# Core429IBaseBoardVerE.net
KiCad netlist of a schematic drawn in Altium Designer
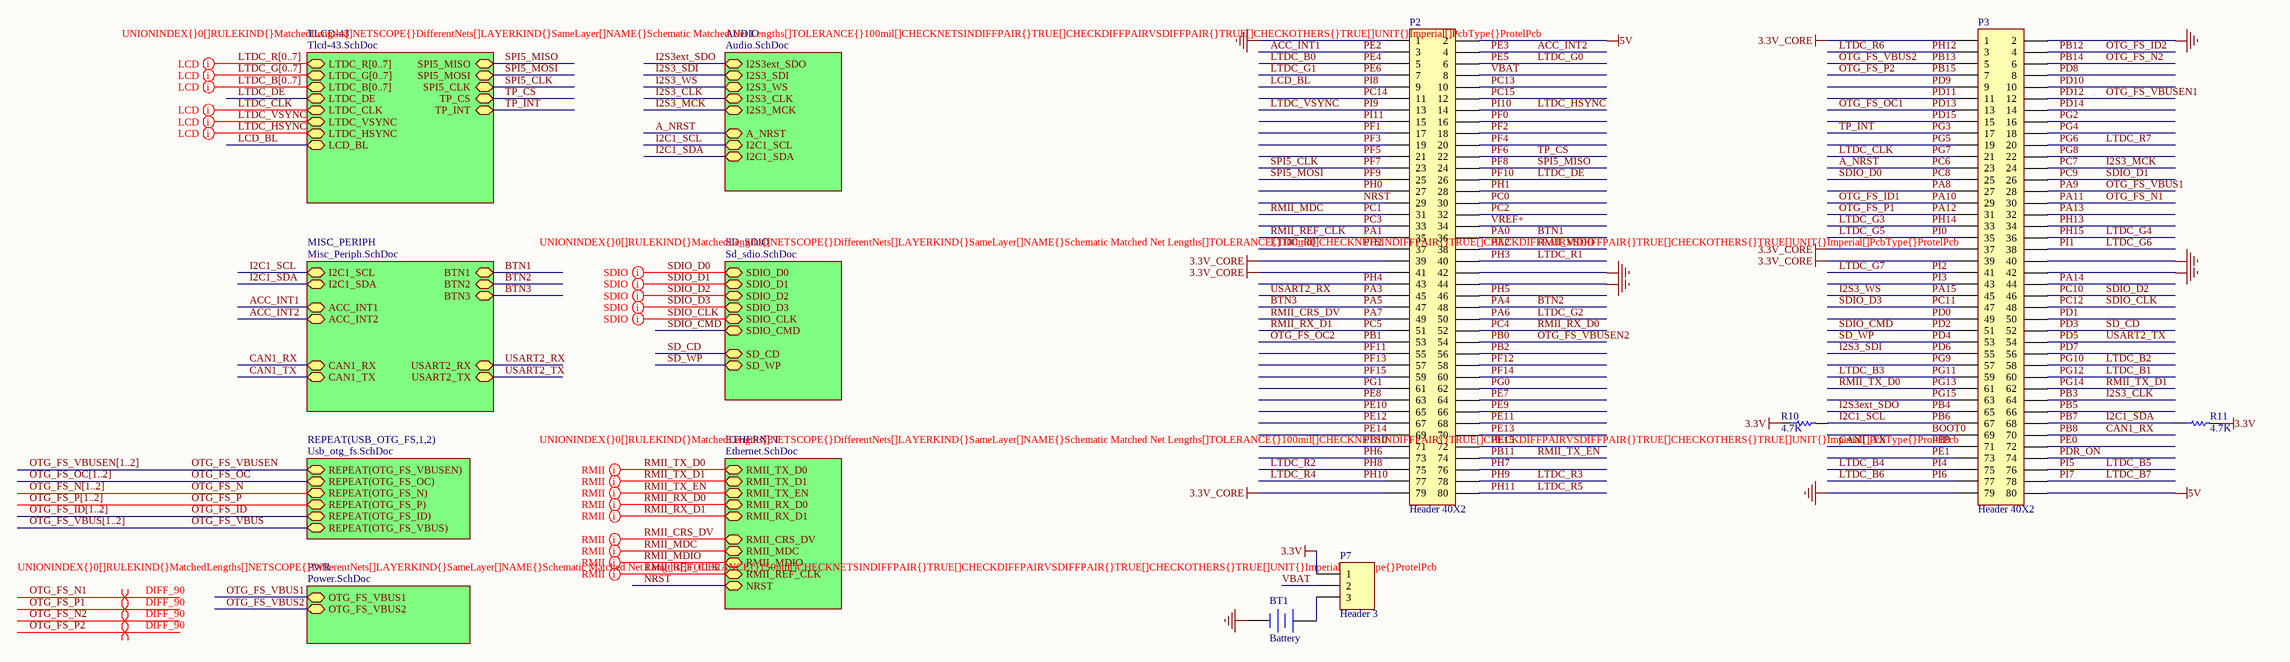
[diagram p0: Core429IBaseBoardVerE.SchDoc]

(export (version "E")
  (design (tool "Eeschema 10.0.6"))
  (components
    (comp (ref "BT1")
      (value "Battery")
      (footprint "PN3000")
      (description "Multicell Battery")
      (libsource (lib "Core429IBaseBoardVerE") (part "Battery"))
    )
    (comp (ref "P2")
      (value "Header 40X2")
      (footprint "SHDR2X40")
      (description "Header, 40-Pin, Dual row")
      (libsource (lib "Core429IBaseBoard") (part "Header 40X2"))
    )
    (comp (ref "P3")
      (value "Header 40X2")
      (footprint "SHDR2X40")
      (description "Header, 40-Pin, Dual row")
      (libsource (lib "Core429IBaseBoard") (part "Header 40X2"))
    )
    (comp (ref "P7")
      (value "Header 3")
      (footprint "HDR1X3")
      (description "Header, 3-Pin")
      (libsource (lib "Core429IBaseBoardVerE") (part "Header 3"))
    )
    (comp (ref "R10")
      (value "4.7K")
      (footprint "RESC2012N")
      (description "Resistor")
      (fields (field (name "Comment") "Res"))
      (libsource (lib "Core429IBaseBoardVerE") (part "Res"))
    )
    (comp (ref "R11")
      (value "4.7K")
      (footprint "RESC2012N")
      (description "Resistor")
      (fields (field (name "Comment") "Res"))
      (libsource (lib "Core429IBaseBoardVerE") (part "Res"))
    )
  )
  (nets
    (net (code "1") (name "/ACC_INT1") (class "Default")
      (node (ref "P2") (pin "3") (pinfunction "3_3") (pintype "passive"))
    )
    (net (code "2") (name "/ACC_INT2") (class "Default")
      (node (ref "P2") (pin "4") (pinfunction "4_4") (pintype "passive"))
    )
    (net (code "3") (name "/A_NRST") (class "Default")
      (node (ref "P3") (pin "23") (pinfunction "23_23") (pintype "passive"))
    )
    (net (code "4") (name "/BOOT0") (class "Default")
      (node (ref "P3") (pin "69") (pinfunction "69_69") (pintype "passive"))
    )
    (net (code "5") (name "/BTN1") (class "Default")
      (node (ref "P2") (pin "36") (pinfunction "36_36") (pintype "passive"))
    )
    (net (code "6") (name "/BTN2") (class "Default")
      (node (ref "P2") (pin "48") (pinfunction "48_48") (pintype "passive"))
    )
    (net (code "7") (name "/BTN3") (class "Default")
      (node (ref "P2") (pin "47") (pinfunction "47_47") (pintype "passive"))
    )
    (net (code "8") (name "/CAN1_RX") (class "Default")
      (node (ref "P3") (pin "70") (pinfunction "70_70") (pintype "passive"))
    )
    (net (code "9") (name "/CAN1_TX") (class "Default")
      (node (ref "P3") (pin "71") (pinfunction "71_71") (pintype "passive"))
    )
    (net (code "10") (name "/I2C1_SCL") (class "Default")
      (node (ref "P3") (pin "67") (pinfunction "67_67") (pintype "passive"))
      (node (ref "R10") (pin "2") (pinfunction "2_2") (pintype "passive"))
    )
    (net (code "11") (name "/I2C1_SDA") (class "Default")
      (node (ref "P3") (pin "68") (pinfunction "68_68") (pintype "passive"))
      (node (ref "R11") (pin "1") (pinfunction "1_1") (pintype "passive"))
    )
    (net (code "12") (name "/I2S3_CLK") (class "Default")
      (node (ref "P3") (pin "64") (pinfunction "64_64") (pintype "passive"))
    )
    (net (code "13") (name "/I2S3_MCK") (class "Default")
      (node (ref "P3") (pin "24") (pinfunction "24_24") (pintype "passive"))
    )
    (net (code "14") (name "/I2S3_SDI") (class "Default")
      (node (ref "P3") (pin "55") (pinfunction "55_55") (pintype "passive"))
    )
    (net (code "15") (name "/I2S3_WS") (class "Default")
      (node (ref "P3") (pin "45") (pinfunction "45_45") (pintype "passive"))
    )
    (net (code "16") (name "/I2S3ext_SDO") (class "Default")
      (node (ref "P3") (pin "65") (pinfunction "65_65") (pintype "passive"))
    )
    (net (code "17") (name "/LCD_BL") (class "Default")
      (node (ref "P2") (pin "9") (pinfunction "9_9") (pintype "passive"))
    )
    (net (code "18") (name "/LTDC_B0") (class "Default")
      (node (ref "P2") (pin "5") (pinfunction "5_5") (pintype "passive"))
    )
    (net (code "19") (name "/LTDC_B1") (class "Default")
      (node (ref "P3") (pin "60") (pinfunction "60_60") (pintype "passive"))
    )
    (net (code "20") (name "/LTDC_B2") (class "Default")
      (node (ref "P3") (pin "58") (pinfunction "58_58") (pintype "passive"))
    )
    (net (code "21") (name "/LTDC_B3") (class "Default")
      (node (ref "P3") (pin "59") (pinfunction "59_59") (pintype "passive"))
    )
    (net (code "22") (name "/LTDC_B4") (class "Default")
      (node (ref "P3") (pin "75") (pinfunction "75_75") (pintype "passive"))
    )
    (net (code "23") (name "/LTDC_B5") (class "Default")
      (node (ref "P3") (pin "76") (pinfunction "76_76") (pintype "passive"))
    )
    (net (code "24") (name "/LTDC_B6") (class "Default")
      (node (ref "P3") (pin "77") (pinfunction "77_77") (pintype "passive"))
    )
    (net (code "25") (name "/LTDC_B7") (class "Default")
      (node (ref "P3") (pin "78") (pinfunction "78_78") (pintype "passive"))
    )
    (net (code "27") (name "/LTDC_CLK") (class "Default")
      (node (ref "P3") (pin "21") (pinfunction "21_21") (pintype "passive"))
    )
    (net (code "28") (name "/LTDC_DE") (class "Default")
      (node (ref "P2") (pin "26") (pinfunction "26_26") (pintype "passive"))
    )
    (net (code "29") (name "/LTDC_G0") (class "Default")
      (node (ref "P2") (pin "6") (pinfunction "6_6") (pintype "passive"))
    )
    (net (code "30") (name "/LTDC_G1") (class "Default")
      (node (ref "P2") (pin "7") (pinfunction "7_7") (pintype "passive"))
    )
    (net (code "31") (name "/LTDC_G2") (class "Default")
      (node (ref "P2") (pin "50") (pinfunction "50_50") (pintype "passive"))
    )
    (net (code "32") (name "/LTDC_G3") (class "Default")
      (node (ref "P3") (pin "33") (pinfunction "33_33") (pintype "passive"))
    )
    (net (code "33") (name "/LTDC_G4") (class "Default")
      (node (ref "P3") (pin "36") (pinfunction "36_36") (pintype "passive"))
    )
    (net (code "34") (name "/LTDC_G5") (class "Default")
      (node (ref "P3") (pin "35") (pinfunction "35_35") (pintype "passive"))
    )
    (net (code "35") (name "/LTDC_G6") (class "Default")
      (node (ref "P3") (pin "38") (pinfunction "38_38") (pintype "passive"))
    )
    (net (code "36") (name "/LTDC_G7") (class "Default")
      (node (ref "P3") (pin "41") (pinfunction "41_41") (pintype "passive"))
    )
    (net (code "38") (name "/LTDC_HSYNC") (class "Default")
      (node (ref "P2") (pin "14") (pinfunction "14_14") (pintype "passive"))
    )
    (net (code "39") (name "/LTDC_R0") (class "Default")
      (node (ref "P2") (pin "37") (pinfunction "37_37") (pintype "passive"))
    )
    (net (code "40") (name "/LTDC_R1") (class "Default")
      (node (ref "P2") (pin "40") (pinfunction "40_40") (pintype "passive"))
    )
    (net (code "41") (name "/LTDC_R2") (class "Default")
      (node (ref "P2") (pin "75") (pinfunction "75_75") (pintype "passive"))
    )
    (net (code "42") (name "/LTDC_R3") (class "Default")
      (node (ref "P2") (pin "78") (pinfunction "78_78") (pintype "passive"))
    )
    (net (code "43") (name "/LTDC_R4") (class "Default")
      (node (ref "P2") (pin "77") (pinfunction "77_77") (pintype "passive"))
    )
    (net (code "44") (name "/LTDC_R5") (class "Default")
      (node (ref "P2") (pin "80") (pinfunction "80_80") (pintype "passive"))
    )
    (net (code "45") (name "/LTDC_R6") (class "Default")
      (node (ref "P3") (pin "3") (pinfunction "3_3") (pintype "passive"))
    )
    (net (code "46") (name "/LTDC_R7") (class "Default")
      (node (ref "P3") (pin "20") (pinfunction "20_20") (pintype "passive"))
    )
    (net (code "48") (name "/LTDC_VSYNC") (class "Default")
      (node (ref "P2") (pin "13") (pinfunction "13_13") (pintype "passive"))
    )
    (net (code "49") (name "/NRST") (class "Default")
      (node (ref "P2") (pin "29") (pinfunction "29_29") (pintype "passive"))
    )
    (net (code "51") (name "/OTG_FS_ID1") (class "Default")
      (node (ref "P3") (pin "29") (pinfunction "29_29") (pintype "passive"))
    )
    (net (code "52") (name "/OTG_FS_ID2") (class "Default")
      (node (ref "P3") (pin "4") (pinfunction "4_4") (pintype "passive"))
    )
    (net (code "55") (name "/OTG_FS_N1") (class "Default")
      (node (ref "P3") (pin "30") (pinfunction "30_30") (pintype "passive"))
    )
    (net (code "56") (name "/OTG_FS_N2") (class "Default")
      (node (ref "P3") (pin "6") (pinfunction "6_6") (pintype "passive"))
    )
    (net (code "59") (name "/OTG_FS_OC1") (class "Default")
      (node (ref "P3") (pin "13") (pinfunction "13_13") (pintype "passive"))
    )
    (net (code "60") (name "/OTG_FS_OC2") (class "Default")
      (node (ref "P2") (pin "53") (pinfunction "53_53") (pintype "passive"))
    )
    (net (code "63") (name "/OTG_FS_P1") (class "Default")
      (node (ref "P3") (pin "31") (pinfunction "31_31") (pintype "passive"))
    )
    (net (code "64") (name "/OTG_FS_P2") (class "Default")
      (node (ref "P3") (pin "7") (pinfunction "7_7") (pintype "passive"))
    )
    (net (code "67") (name "/OTG_FS_VBUS1") (class "Default")
      (node (ref "P3") (pin "28") (pinfunction "28_28") (pintype "passive"))
    )
    (net (code "68") (name "/OTG_FS_VBUS2") (class "Default")
      (node (ref "P3") (pin "5") (pinfunction "5_5") (pintype "passive"))
    )
    (net (code "70") (name "/OTG_FS_VBUSEN1") (class "Default")
      (node (ref "P3") (pin "12") (pinfunction "12_12") (pintype "passive"))
    )
    (net (code "71") (name "/OTG_FS_VBUSEN2") (class "Default")
      (node (ref "P2") (pin "54") (pinfunction "54_54") (pintype "passive"))
    )
    (net (code "74") (name "/PA1") (class "Default")
      (node (ref "P2") (pin "35") (pinfunction "35_35") (pintype "passive"))
    )
    (net (code "75") (name "/PA2") (class "Default")
      (node (ref "P2") (pin "38") (pinfunction "38_38") (pintype "passive"))
    )
    (net (code "76") (name "/PA3") (class "Default")
      (node (ref "P2") (pin "45") (pinfunction "45_45") (pintype "passive"))
    )
    (net (code "77") (name "/PA7") (class "Default")
      (node (ref "P2") (pin "49") (pinfunction "49_49") (pintype "passive"))
    )
    (net (code "78") (name "/PA8") (class "Default")
      (node (ref "P3") (pin "27") (pinfunction "27_27") (pintype "passive"))
    )
    (net (code "79") (name "/PA13") (class "Default")
      (node (ref "P3") (pin "32") (pinfunction "32_32") (pintype "passive"))
    )
    (net (code "80") (name "/PA14") (class "Default")
      (node (ref "P3") (pin "44") (pinfunction "44_44") (pintype "passive"))
    )
    (net (code "81") (name "/PB2") (class "Default")
      (node (ref "P2") (pin "56") (pinfunction "56_56") (pintype "passive"))
    )
    (net (code "82") (name "/PB5") (class "Default")
      (node (ref "P3") (pin "66") (pinfunction "66_66") (pintype "passive"))
    )
    (net (code "83") (name "/PB10") (class "Default")
      (node (ref "P2") (pin "71") (pinfunction "71_71") (pintype "passive"))
    )
    (net (code "84") (name "/PB11") (class "Default")
      (node (ref "P2") (pin "74") (pinfunction "74_74") (pintype "passive"))
    )
    (net (code "85") (name "/PC0") (class "Default")
      (node (ref "P2") (pin "30") (pinfunction "30_30") (pintype "passive"))
    )
    (net (code "86") (name "/PC1") (class "Default")
      (node (ref "P2") (pin "31") (pinfunction "31_31") (pintype "passive"))
    )
    (net (code "87") (name "/PC2") (class "Default")
      (node (ref "P2") (pin "32") (pinfunction "32_32") (pintype "passive"))
    )
    (net (code "88") (name "/PC3") (class "Default")
      (node (ref "P2") (pin "33") (pinfunction "33_33") (pintype "passive"))
    )
    (net (code "89") (name "/PC4") (class "Default")
      (node (ref "P2") (pin "52") (pinfunction "52_52") (pintype "passive"))
    )
    (net (code "90") (name "/PC5") (class "Default")
      (node (ref "P2") (pin "51") (pinfunction "51_51") (pintype "passive"))
    )
    (net (code "91") (name "/PC8") (class "Default")
      (node (ref "P3") (pin "25") (pinfunction "25_25") (pintype "passive"))
    )
    (net (code "92") (name "/PC9") (class "Default")
      (node (ref "P3") (pin "26") (pinfunction "26_26") (pintype "passive"))
    )
    (net (code "93") (name "/PC10") (class "Default")
      (node (ref "P3") (pin "46") (pinfunction "46_46") (pintype "passive"))
    )
    (net (code "94") (name "/PC11") (class "Default")
      (node (ref "P3") (pin "47") (pinfunction "47_47") (pintype "passive"))
    )
    (net (code "95") (name "/PC12") (class "Default")
      (node (ref "P3") (pin "48") (pinfunction "48_48") (pintype "passive"))
    )
    (net (code "96") (name "/PC13") (class "Default")
      (node (ref "P2") (pin "10") (pinfunction "10_10") (pintype "passive"))
    )
    (net (code "97") (name "/PC14") (class "Default")
      (node (ref "P2") (pin "11") (pinfunction "11_11") (pintype "passive"))
    )
    (net (code "98") (name "/PC15") (class "Default")
      (node (ref "P2") (pin "12") (pinfunction "12_12") (pintype "passive"))
    )
    (net (code "99") (name "/PD0") (class "Default")
      (node (ref "P3") (pin "49") (pinfunction "49_49") (pintype "passive"))
    )
    (net (code "100") (name "/PD1") (class "Default")
      (node (ref "P3") (pin "50") (pinfunction "50_50") (pintype "passive"))
    )
    (net (code "101") (name "/PD2") (class "Default")
      (node (ref "P3") (pin "51") (pinfunction "51_51") (pintype "passive"))
    )
    (net (code "102") (name "/PD3") (class "Default")
      (node (ref "P3") (pin "52") (pinfunction "52_52") (pintype "passive"))
    )
    (net (code "103") (name "/PD4") (class "Default")
      (node (ref "P3") (pin "53") (pinfunction "53_53") (pintype "passive"))
    )
    (net (code "104") (name "/PD5") (class "Default")
      (node (ref "P3") (pin "54") (pinfunction "54_54") (pintype "passive"))
    )
    (net (code "105") (name "/PD7") (class "Default")
      (node (ref "P3") (pin "56") (pinfunction "56_56") (pintype "passive"))
    )
    (net (code "106") (name "/PD8") (class "Default")
      (node (ref "P3") (pin "8") (pinfunction "8_8") (pintype "passive"))
    )
    (net (code "107") (name "/PD9") (class "Default")
      (node (ref "P3") (pin "9") (pinfunction "9_9") (pintype "passive"))
    )
    (net (code "108") (name "/PD10") (class "Default")
      (node (ref "P3") (pin "10") (pinfunction "10_10") (pintype "passive"))
    )
    (net (code "109") (name "/PD11") (class "Default")
      (node (ref "P3") (pin "11") (pinfunction "11_11") (pintype "passive"))
    )
    (net (code "110") (name "/PD14") (class "Default")
      (node (ref "P3") (pin "14") (pinfunction "14_14") (pintype "passive"))
    )
    (net (code "111") (name "/PD15") (class "Default")
      (node (ref "P3") (pin "15") (pinfunction "15_15") (pintype "passive"))
    )
    (net (code "112") (name "/PDR_ON") (class "Default")
      (node (ref "P3") (pin "74") (pinfunction "74_74") (pintype "passive"))
    )
    (net (code "113") (name "/PE0") (class "Default")
      (node (ref "P3") (pin "72") (pinfunction "72_72") (pintype "passive"))
    )
    (net (code "114") (name "/PE1") (class "Default")
      (node (ref "P3") (pin "73") (pinfunction "73_73") (pintype "passive"))
    )
    (net (code "115") (name "/PE7") (class "Default")
      (node (ref "P2") (pin "64") (pinfunction "64_64") (pintype "passive"))
    )
    (net (code "116") (name "/PE8") (class "Default")
      (node (ref "P2") (pin "63") (pinfunction "63_63") (pintype "passive"))
    )
    (net (code "117") (name "/PE9") (class "Default")
      (node (ref "P2") (pin "66") (pinfunction "66_66") (pintype "passive"))
    )
    (net (code "118") (name "/PE10") (class "Default")
      (node (ref "P2") (pin "65") (pinfunction "65_65") (pintype "passive"))
    )
    (net (code "119") (name "/PE11") (class "Default")
      (node (ref "P2") (pin "68") (pinfunction "68_68") (pintype "passive"))
    )
    (net (code "120") (name "/PE12") (class "Default")
      (node (ref "P2") (pin "67") (pinfunction "67_67") (pintype "passive"))
    )
    (net (code "121") (name "/PE13") (class "Default")
      (node (ref "P2") (pin "70") (pinfunction "70_70") (pintype "passive"))
    )
    (net (code "122") (name "/PE14") (class "Default")
      (node (ref "P2") (pin "69") (pinfunction "69_69") (pintype "passive"))
    )
    (net (code "123") (name "/PE15") (class "Default")
      (node (ref "P2") (pin "72") (pinfunction "72_72") (pintype "passive"))
    )
    (net (code "124") (name "/PF0") (class "Default")
      (node (ref "P2") (pin "16") (pinfunction "16_16") (pintype "passive"))
    )
    (net (code "125") (name "/PF1") (class "Default")
      (node (ref "P2") (pin "17") (pinfunction "17_17") (pintype "passive"))
    )
    (net (code "126") (name "/PF2") (class "Default")
      (node (ref "P2") (pin "18") (pinfunction "18_18") (pintype "passive"))
    )
    (net (code "127") (name "/PF3") (class "Default")
      (node (ref "P2") (pin "19") (pinfunction "19_19") (pintype "passive"))
    )
    (net (code "128") (name "/PF4") (class "Default")
      (node (ref "P2") (pin "20") (pinfunction "20_20") (pintype "passive"))
    )
    (net (code "129") (name "/PF5") (class "Default")
      (node (ref "P2") (pin "21") (pinfunction "21_21") (pintype "passive"))
    )
    (net (code "130") (name "/PF6") (class "Default")
      (node (ref "P2") (pin "22") (pinfunction "22_22") (pintype "passive"))
    )
    (net (code "131") (name "/PF7") (class "Default")
      (node (ref "P2") (pin "23") (pinfunction "23_23") (pintype "passive"))
    )
    (net (code "132") (name "/PF8") (class "Default")
      (node (ref "P2") (pin "24") (pinfunction "24_24") (pintype "passive"))
    )
    (net (code "133") (name "/PF9") (class "Default")
      (node (ref "P2") (pin "25") (pinfunction "25_25") (pintype "passive"))
    )
    (net (code "134") (name "/PF11") (class "Default")
      (node (ref "P2") (pin "55") (pinfunction "55_55") (pintype "passive"))
    )
    (net (code "135") (name "/PF12") (class "Default")
      (node (ref "P2") (pin "58") (pinfunction "58_58") (pintype "passive"))
    )
    (net (code "136") (name "/PF13") (class "Default")
      (node (ref "P2") (pin "57") (pinfunction "57_57") (pintype "passive"))
    )
    (net (code "137") (name "/PF14") (class "Default")
      (node (ref "P2") (pin "60") (pinfunction "60_60") (pintype "passive"))
    )
    (net (code "138") (name "/PF15") (class "Default")
      (node (ref "P2") (pin "59") (pinfunction "59_59") (pintype "passive"))
    )
    (net (code "139") (name "/PG0") (class "Default")
      (node (ref "P2") (pin "62") (pinfunction "62_62") (pintype "passive"))
    )
    (net (code "140") (name "/PG1") (class "Default")
      (node (ref "P2") (pin "61") (pinfunction "61_61") (pintype "passive"))
    )
    (net (code "141") (name "/PG2") (class "Default")
      (node (ref "P3") (pin "16") (pinfunction "16_16") (pintype "passive"))
    )
    (net (code "142") (name "/PG3") (class "Default")
      (node (ref "P3") (pin "17") (pinfunction "17_17") (pintype "passive"))
    )
    (net (code "143") (name "/PG4") (class "Default")
      (node (ref "P3") (pin "18") (pinfunction "18_18") (pintype "passive"))
    )
    (net (code "144") (name "/PG5") (class "Default")
      (node (ref "P3") (pin "19") (pinfunction "19_19") (pintype "passive"))
    )
    (net (code "145") (name "/PG8") (class "Default")
      (node (ref "P3") (pin "22") (pinfunction "22_22") (pintype "passive"))
    )
    (net (code "146") (name "/PG9") (class "Default")
      (node (ref "P3") (pin "57") (pinfunction "57_57") (pintype "passive"))
    )
    (net (code "147") (name "/PG13") (class "Default")
      (node (ref "P3") (pin "61") (pinfunction "61_61") (pintype "passive"))
    )
    (net (code "148") (name "/PG14") (class "Default")
      (node (ref "P3") (pin "62") (pinfunction "62_62") (pintype "passive"))
    )
    (net (code "149") (name "/PG15") (class "Default")
      (node (ref "P3") (pin "63") (pinfunction "63_63") (pintype "passive"))
    )
    (net (code "150") (name "/PH0") (class "Default")
      (node (ref "P2") (pin "27") (pinfunction "27_27") (pintype "passive"))
    )
    (net (code "151") (name "/PH1") (class "Default")
      (node (ref "P2") (pin "28") (pinfunction "28_28") (pintype "passive"))
    )
    (net (code "152") (name "/PH4") (class "Default")
      (node (ref "P2") (pin "43") (pinfunction "43_43") (pintype "passive"))
    )
    (net (code "153") (name "/PH5") (class "Default")
      (node (ref "P2") (pin "46") (pinfunction "46_46") (pintype "passive"))
    )
    (net (code "154") (name "/PH6") (class "Default")
      (node (ref "P2") (pin "73") (pinfunction "73_73") (pintype "passive"))
    )
    (net (code "155") (name "/PH7") (class "Default")
      (node (ref "P2") (pin "76") (pinfunction "76_76") (pintype "passive"))
    )
    (net (code "156") (name "/PH13") (class "Default")
      (node (ref "P3") (pin "34") (pinfunction "34_34") (pintype "passive"))
    )
    (net (code "157") (name "/PI3") (class "Default")
      (node (ref "P3") (pin "43") (pinfunction "43_43") (pintype "passive"))
    )
    (net (code "158") (name "/PI11") (class "Default")
      (node (ref "P2") (pin "15") (pinfunction "15_15") (pintype "passive"))
    )
    (net (code "159") (name "/VBAT") (class "Default")
      (node (ref "P2") (pin "8") (pinfunction "8_8") (pintype "passive"))
      (node (ref "P7") (pin "2") (pinfunction "2_2") (pintype "passive"))
    )
    (net (code "160") (name "/VREF+") (class "Default")
      (node (ref "P2") (pin "34") (pinfunction "34_34") (pintype "passive"))
    )
    (net (code "161") (name "3.3V") (class "Default")
      (node (ref "P7") (pin "1") (pinfunction "1_1") (pintype "passive"))
      (node (ref "R10") (pin "1") (pinfunction "1_1") (pintype "passive"))
      (node (ref "R11") (pin "2") (pinfunction "2_2") (pintype "passive"))
    )
    (net (code "162") (name "3.3V_CORE") (class "Default")
      (node (ref "P2") (pin "39") (pinfunction "39_39") (pintype "passive"))
      (node (ref "P2") (pin "41") (pinfunction "41_41") (pintype "passive"))
      (node (ref "P2") (pin "79") (pinfunction "79_79") (pintype "passive"))
      (node (ref "P3") (pin "1") (pinfunction "1_1") (pintype "passive"))
      (node (ref "P3") (pin "37") (pinfunction "37_37") (pintype "passive"))
      (node (ref "P3") (pin "39") (pinfunction "39_39") (pintype "passive"))
    )
    (net (code "163") (name "5V") (class "Default")
      (node (ref "P2") (pin "2") (pinfunction "2_2") (pintype "passive"))
      (node (ref "P3") (pin "80") (pinfunction "80_80") (pintype "passive"))
    )
    (net (code "164") (name "DGND") (class "Default")
      (node (ref "BT1") (pin "2") (pinfunction "-_2") (pintype "passive"))
      (node (ref "P2") (pin "1") (pinfunction "1_1") (pintype "passive"))
      (node (ref "P2") (pin "42") (pinfunction "42_42") (pintype "passive"))
      (node (ref "P2") (pin "44") (pinfunction "44_44") (pintype "passive"))
      (node (ref "P3") (pin "2") (pinfunction "2_2") (pintype "passive"))
      (node (ref "P3") (pin "40") (pinfunction "40_40") (pintype "passive"))
      (node (ref "P3") (pin "42") (pinfunction "42_42") (pintype "passive"))
      (node (ref "P3") (pin "79") (pinfunction "79_79") (pintype "passive"))
    )
    (net (code "165") (name "Net-(BT1-+)") (class "Default")
      (node (ref "BT1") (pin "1") (pinfunction "+_1") (pintype "passive"))
      (node (ref "P7") (pin "3") (pinfunction "3_3") (pintype "passive"))
    )
  )
)
